# IMU_Board.net
KiCad netlist of a schematic drawn in Altium Designer
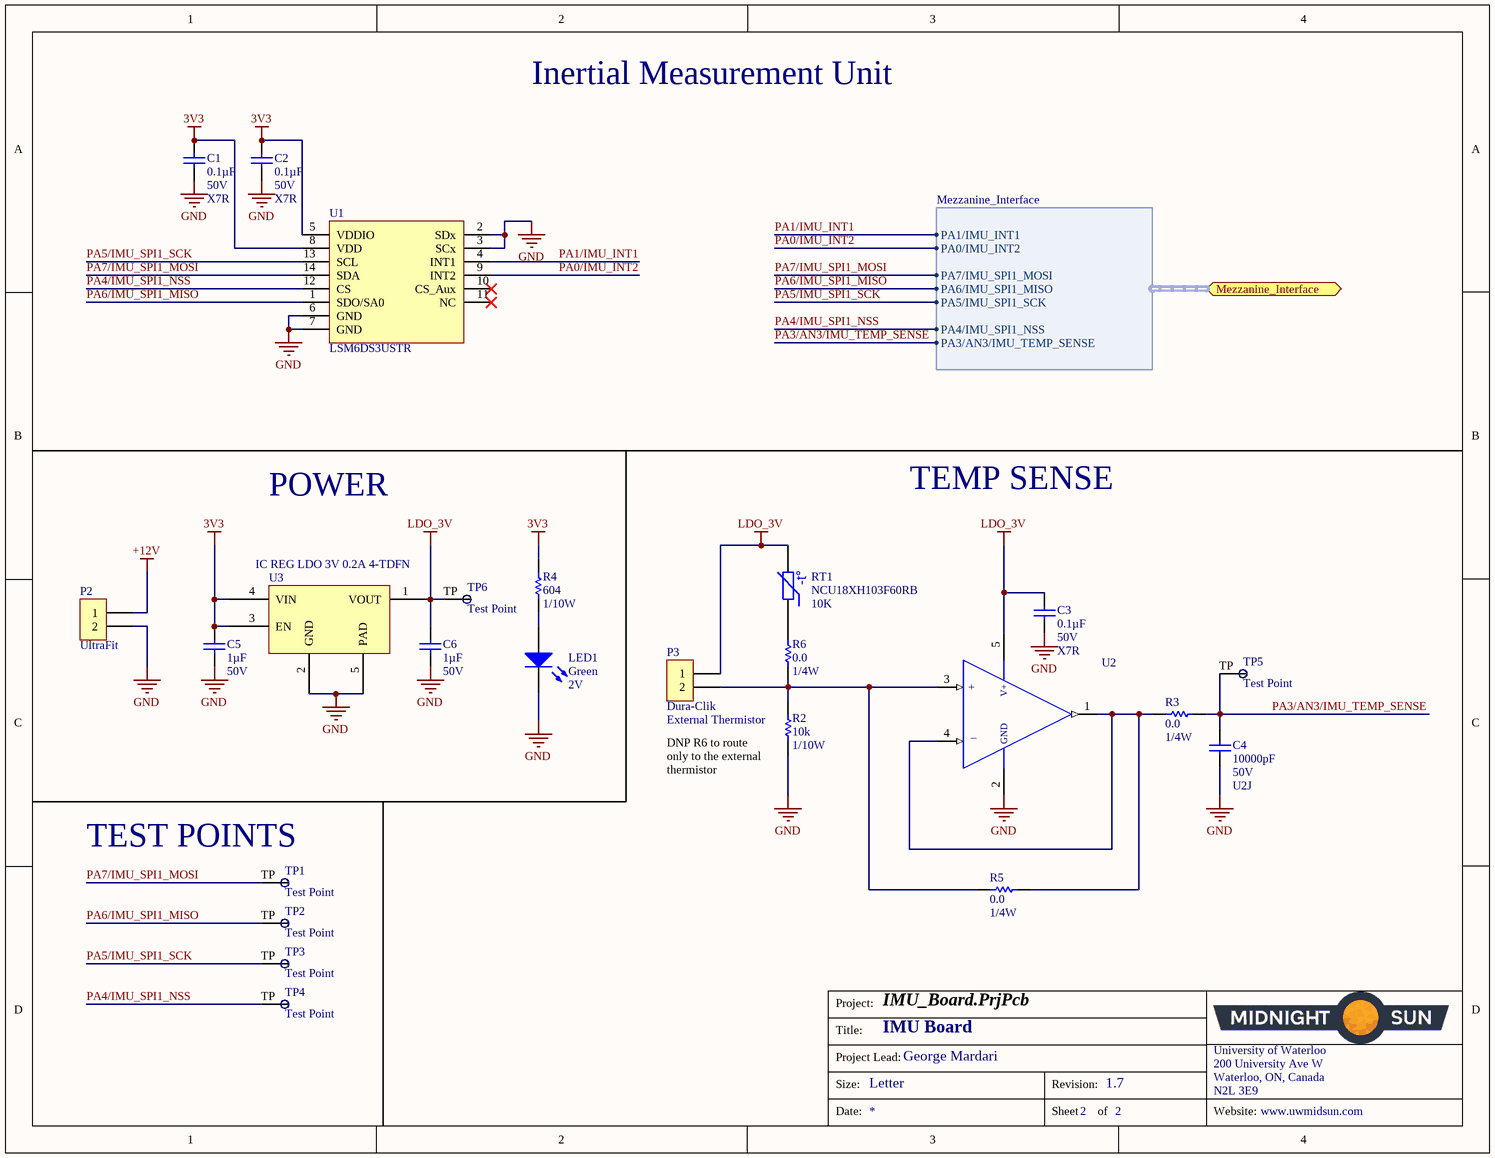
[diagram p0: IMU_Board.SchDoc]

(export (version "E")
  (design (tool "Eeschema 10.0.6"))
  (components
    (comp (ref "C1")
      (value "CAP CER 0.1UF 50V 10% X7R 0603")
      (footprint "CAP, 0603")
      (description "0.10µF ±10% 50V Ceramic Capacitor X7R 0603 (1608 Metric)")
      (fields
        (field (name "TOLERANCE") "±10%")
        (field (name "CAPACITANCE") "0.1µF")
        (field (name "VOLTAGE") "50V")
        (field (name "TEMPERATURE COEFFICIENT") "X7R")
      )
      (libsource (lib "Schematic Diagrams") (part "CAP CER 0.1UF 50V 10% X7R 0603"))
    )
    (comp (ref "C2")
      (value "CAP CER 0.1UF 50V 10% X7R 0603")
      (footprint "CAP, 0603")
      (description "0.10µF ±10% 50V Ceramic Capacitor X7R 0603 (1608 Metric)")
      (fields
        (field (name "TOLERANCE") "±10%")
        (field (name "CAPACITANCE") "0.1µF")
        (field (name "VOLTAGE") "50V")
        (field (name "TEMPERATURE COEFFICIENT") "X7R")
      )
      (libsource (lib "Schematic Diagrams") (part "CAP CER 0.1UF 50V 10% X7R 0603"))
    )
    (comp (ref "C3")
      (value "CAP CER 0.1UF 50V 10% X7R 0603")
      (footprint "CAP, 0603")
      (description "0.10µF ±10% 50V Ceramic Capacitor X7R 0603 (1608 Metric)")
      (fields
        (field (name "TOLERANCE") "±10%")
        (field (name "CAPACITANCE") "0.1µF")
        (field (name "VOLTAGE") "50V")
        (field (name "TEMPERATURE COEFFICIENT") "X7R")
      )
      (libsource (lib "Schematic Diagrams") (part "CAP CER 0.1UF 50V 10% X7R 0603"))
    )
    (comp (ref "C4")
      (value "CAP CER 10nF 50V 5% X7R 0603")
      (footprint "CAP, 0603")
      (description "10000pF ±5% 50V Ceramic Capacitor U2J 0603 (1608 Metric)")
      (fields
        (field (name "TOLERANCE") "±5%")
        (field (name "CAPACITANCE") "10000pF")
        (field (name "VOLTAGE") "50V")
        (field (name "TEMPERATURE COEFFICIENT") "U2J")
      )
      (libsource (lib "Schematic Diagrams") (part "CAP CER 10nF 50V 5% X7R 0603"))
    )
    (comp (ref "C5")
      (value "CAP CER 1UF 50V 10% X7R 0603")
      (footprint "CAP, 0603")
      (description "1µF ±10% 50V Ceramic Capacitor X7R 0603 (1608 Metric)")
      (fields
        (field (name "TOLERANCE") "±10%")
        (field (name "CAPACITANCE") "1µF")
        (field (name "VOLTAGE") "50V")
      )
      (libsource (lib "Schematic Diagrams") (part "CAP CER 1UF 50V 10% X7R 0603"))
    )
    (comp (ref "C6")
      (value "CAP CER 1UF 50V 10% X7R 0603")
      (footprint "CAP, 0603")
      (description "1µF ±10% 50V Ceramic Capacitor X7R 0603 (1608 Metric)")
      (fields
        (field (name "TOLERANCE") "±10%")
        (field (name "CAPACITANCE") "1µF")
        (field (name "VOLTAGE") "50V")
      )
      (libsource (lib "Schematic Diagrams") (part "CAP CER 1UF 50V 10% X7R 0603"))
    )
    (comp (ref "LED1")
      (value "LED GREEN CLEAR 2V 0603")
      (footprint "LED_0603")
      (description "Green 572nm LED Indication - Discrete 2V 0603 (1608 Metric)")
      (fields
        (field (name "MANUFACTURER") "Wurth Electronics Inc.")
        (field (name "MANUFACTURER PART NUMBER") "150060VS75000")
        (field (name "COLOR") "Green")
        (field (name "VOLTAGE - FORWARD (VF) (TYP)") "2V")
      )
      (libsource (lib "Schematic Diagrams") (part "LED GREEN CLEAR 2V 0603"))
    )
    (comp (ref "P2")
      (value "CONN 2POS ULTRA-FIT 0.138\"")
      (footprint "CONN, 2POS ULTRA-FIT")
      (description "2 Positions Header, Shrouded Connector 0.138\" (3.50mm) Through Hole Gold")
      (fields (field (name "VOLTAGE") "400V") (field (name "SERIES") "UltraFit"))
      (libsource (lib "Schematic Diagrams") (part "CONN 2POS ULTRA-FIT 0.138{dblquote}"))
    )
    (comp (ref "P3")
      (value "Dura-Clik")
      (footprint "CONN, 2POS Dura-Click Vertical")
      (description "2 Positions Header, Shrouded Connector 0.079\" (2.00mm) Surface Mount, Vertical Tin")
      (fields
        (field (name "MANUFACTURER") "Molex, LLC")
        (field (name "MANUFACTURER PART NUMBER") "5600200220")
      )
      (libsource (lib "Schematic Diagrams") (part "CONN 2POS DURA-CLIK 0.079{dblquote} VERT"))
    )
    (comp (ref "R2")
      (value "RES 10K OHM 1% 1/10W 0603")
      (footprint "RES, 0603")
      (description "RES SMD 10K OHM 1% 1/10W 0603")
      (fields
        (field (name "TOLERANCE") "±1%")
        (field (name "RESISTANCE") "10k")
        (field (name "POWER") "1/10W")
      )
      (libsource (lib "Schematic Diagrams") (part "RES 10K OHM 1% 1/10W 0603"))
    )
    (comp (ref "R3")
      (value "RES 0.0 OHM 1/4W 0603")
      (footprint "RES, 0603")
      (description "RES SMD 0.0 OHM JUMPER 1/4W 0603")
      (fields (field (name "RESISTANCE") "0.0") (field (name "POWER (WATTS)") "1/4W"))
      (libsource (lib "Schematic Diagrams") (part "RES 0.0 OHM 1/4W 0603"))
    )
    (comp (ref "R4")
      (value "RES 604 OHM 1% 1/10W 0603")
      (footprint "RES, 0603")
      (description "RES SMD 604 OHM 1% 1/10W 0603")
      (fields
        (field (name "TOLERANCE") "±1%")
        (field (name "RESISTANCE") "604")
        (field (name "POWER") "1/10W")
      )
      (libsource (lib "Schematic Diagrams") (part "RES 604 OHM 1% 1/10W 0603"))
    )
    (comp (ref "R5")
      (value "RES 0.0 OHM 1/4W 0603")
      (footprint "RES, 0603")
      (description "RES SMD 0.0 OHM JUMPER 1/4W 0603")
      (fields (field (name "RESISTANCE") "0.0") (field (name "POWER (WATTS)") "1/4W"))
      (libsource (lib "Schematic Diagrams") (part "RES 0.0 OHM 1/4W 0603"))
    )
    (comp (ref "R6")
      (value "RES 0.0 OHM 1/4W 0603")
      (footprint "RES, 0603")
      (description "RES SMD 0.0 OHM JUMPER 1/4W 0603")
      (fields (field (name "RESISTANCE") "0.0") (field (name "POWER (WATTS)") "1/4W"))
      (libsource (lib "Schematic Diagrams") (part "RES 0.0 OHM 1/4W 0603"))
    )
    (comp (ref "RT1")
      (value "NTC THERMISTORS 10K 0603 SMD")
      (footprint "RES, 0603")
      (description "NTC THERMISTORS 10KOHM 1608 SMD")
      (fields
        (field (name "MANUFACTURER") "Murata Electronics North America")
        (field (name "MANUFACTURER PART NUMBER") "NCU18XH103F60RB")
        (field (name "RESISTANCE") "10K")
      )
      (libsource (lib "Schematic Diagrams") (part "NTC THERMISTORS 10K 0603 SMD"))
    )
    (comp (ref "TP1")
      (value "Test Point")
      (footprint "Test Point")
      (libsource (lib "Schematic Diagrams") (part "Test Point"))
    )
    (comp (ref "TP2")
      (value "Test Point")
      (footprint "Test Point")
      (libsource (lib "Schematic Diagrams") (part "Test Point"))
    )
    (comp (ref "TP3")
      (value "Test Point")
      (footprint "Test Point")
      (libsource (lib "Schematic Diagrams") (part "Test Point"))
    )
    (comp (ref "TP4")
      (value "Test Point")
      (footprint "Test Point")
      (libsource (lib "Schematic Diagrams") (part "Test Point"))
    )
    (comp (ref "TP5")
      (value "Test Point")
      (footprint "Test Point")
      (libsource (lib "Schematic Diagrams") (part "Test Point"))
    )
    (comp (ref "TP6")
      (value "Test Point")
      (footprint "Test Point")
      (libsource (lib "Schematic Diagrams") (part "Test Point"))
    )
    (comp (ref "U1")
      (value "IC SENSOR IMU LGA-14L")
      (footprint "IC SENSOR IMU LGA-14L")
      (description "Accelerometer, Gyroscope, 3 Axis Sensor I²C, SPI Output")
      (fields
        (field (name "MANUFACTURER") "STMicroelectronics")
        (field (name "MANUFACTURER PART NUMBER") "LSM6DS3USTR")
      )
      (libsource (lib "Schematic Diagrams") (part "IC SENSOR IMU LGA-14L"))
    )
    (comp (ref "U2")
      (value "IC OP AMP GEN PURPOSE RR 10MHZ SOT-23-5")
      (footprint "IC OP AMP GP RR 10MHZ SOT-23-5")
      (description "General Purpose Amplifier 1 Circuit Rail-to-Rail SOT-23-5")
      (libsource (lib "Schematic Diagrams") (part "IC OP AMP GEN PURPOSE RR 10MHZ SOT-23-5"))
    )
    (comp (ref "U3")
      (value "IC REG LDO 3V 0.2A 4-TDFN")
      (footprint "IC REG LDO 3V 0.2A 4-TDFN")
      (fields
        (field (name "MANUFACTURER") "Microchip Technology")
        (field (name "MANUFACTURER PART NUMBER") "MIC94310-PYMT-TR")
      )
      (libsource (lib "Schematic Diagrams") (part "IC REG LDO 3V 0.2A 4-TDFN"))
    )
  )
  (nets
    (net (code "2") (name "+12V") (class "Default")
      (node (ref "P2") (pin "1") (pinfunction "1_1") (pintype "passive"))
    )
    (net (code "3") (name "/PA0{slash}IMU_INT2") (class "Default")
      (node (ref "U1") (pin "9") (pinfunction "INT2_9") (pintype "passive"))
    )
    (net (code "4") (name "/PA1{slash}IMU_INT1") (class "Default")
      (node (ref "U1") (pin "4") (pinfunction "INT1_4") (pintype "passive"))
    )
    (net (code "5") (name "/PA3{slash}AN3{slash}IMU_TEMP_SENSE") (class "Default")
      (node (ref "C4") (pin "1") (pinfunction "1_1") (pintype "passive"))
      (node (ref "R3") (pin "2") (pinfunction "2_2") (pintype "passive"))
      (node (ref "TP5") (pin "TP") (pinfunction "1_TP") (pintype "passive"))
    )
    (net (code "6") (name "/PA4{slash}IMU_SPI1_NSS") (class "Default")
      (node (ref "TP4") (pin "TP") (pinfunction "1_TP") (pintype "passive"))
      (node (ref "U1") (pin "12") (pinfunction "CS_12") (pintype "passive"))
    )
    (net (code "7") (name "/PA5{slash}IMU_SPI1_SCK") (class "Default")
      (node (ref "TP3") (pin "TP") (pinfunction "1_TP") (pintype "passive"))
      (node (ref "U1") (pin "13") (pinfunction "SCL_13") (pintype "passive"))
    )
    (net (code "8") (name "/PA6{slash}IMU_SPI1_MISO") (class "Default")
      (node (ref "TP2") (pin "TP") (pinfunction "1_TP") (pintype "passive"))
      (node (ref "U1") (pin "1") (pinfunction "SDO/SA0_1") (pintype "passive"))
    )
    (net (code "9") (name "/PA7{slash}IMU_SPI1_MOSI") (class "Default")
      (node (ref "TP1") (pin "TP") (pinfunction "1_TP") (pintype "passive"))
      (node (ref "U1") (pin "14") (pinfunction "SDA_14") (pintype "passive"))
    )
    (net (code "11") (name "3V3") (class "Default")
      (node (ref "C1") (pin "1") (pinfunction "1_1") (pintype "passive"))
      (node (ref "C2") (pin "1") (pinfunction "1_1") (pintype "passive"))
      (node (ref "C5") (pin "1") (pinfunction "1_1") (pintype "passive"))
      (node (ref "R4") (pin "1") (pinfunction "1_1") (pintype "passive"))
      (node (ref "U1") (pin "5") (pinfunction "VDDIO_5") (pintype "passive"))
      (node (ref "U1") (pin "8") (pinfunction "VDD_8") (pintype "passive"))
      (node (ref "U3") (pin "3") (pinfunction "EN_3") (pintype "passive"))
      (node (ref "U3") (pin "4") (pinfunction "VIN_4") (pintype "passive"))
    )
    (net (code "12") (name "GND") (class "Default")
      (node (ref "C1") (pin "2") (pinfunction "2_2") (pintype "passive"))
      (node (ref "C2") (pin "2") (pinfunction "2_2") (pintype "passive"))
      (node (ref "C3") (pin "2") (pinfunction "2_2") (pintype "passive"))
      (node (ref "C4") (pin "2") (pinfunction "2_2") (pintype "passive"))
      (node (ref "C5") (pin "2") (pinfunction "2_2") (pintype "passive"))
      (node (ref "C6") (pin "2") (pinfunction "2_2") (pintype "passive"))
      (node (ref "LED1") (pin "2") (pinfunction "K_2") (pintype "passive"))
      (node (ref "P2") (pin "2") (pinfunction "2_2") (pintype "passive"))
      (node (ref "R2") (pin "1") (pinfunction "1_1") (pintype "passive"))
      (node (ref "U1") (pin "2") (pinfunction "SDx_2") (pintype "passive"))
      (node (ref "U1") (pin "3") (pinfunction "SCx_3") (pintype "passive"))
      (node (ref "U1") (pin "6") (pinfunction "GND_6") (pintype "passive"))
      (node (ref "U1") (pin "7") (pinfunction "GND_7") (pintype "passive"))
      (node (ref "U2") (pin "2") (pinfunction "VSS_2") (pintype "power_in"))
      (node (ref "U3") (pin "2") (pinfunction "GND_2") (pintype "passive"))
      (node (ref "U3") (pin "5") (pinfunction "PAD_5") (pintype "passive"))
    )
    (net (code "13") (name "LDO_3V") (class "Default")
      (node (ref "C3") (pin "1") (pinfunction "1_1") (pintype "passive"))
      (node (ref "C6") (pin "1") (pinfunction "1_1") (pintype "passive"))
      (node (ref "P3") (pin "1") (pinfunction "1_1") (pintype "passive"))
      (node (ref "RT1") (pin "2") (pinfunction "2_2") (pintype "passive"))
      (node (ref "TP6") (pin "TP") (pinfunction "1_TP") (pintype "passive"))
      (node (ref "U2") (pin "5") (pinfunction "VDD_5") (pintype "power_in"))
      (node (ref "U3") (pin "1") (pinfunction "VOUT_1") (pintype "passive"))
    )
    (net (code "14") (name "Net-(LED1-A)") (class "Default")
      (node (ref "LED1") (pin "1") (pinfunction "A_1") (pintype "passive"))
      (node (ref "R4") (pin "2") (pinfunction "2_2") (pintype "passive"))
    )
    (net (code "15") (name "Net-(R6-Pad1)") (class "Default")
      (node (ref "R6") (pin "1") (pinfunction "1_1") (pintype "passive"))
      (node (ref "RT1") (pin "1") (pinfunction "1_1") (pintype "passive"))
    )
    (net (code "16") (name "Net-(U2-+IN)") (class "Default")
      (node (ref "P3") (pin "2") (pinfunction "2_2") (pintype "passive"))
      (node (ref "R2") (pin "2") (pinfunction "2_2") (pintype "passive"))
      (node (ref "R5") (pin "1") (pinfunction "1_1") (pintype "passive"))
      (node (ref "R6") (pin "2") (pinfunction "2_2") (pintype "passive"))
      (node (ref "U2") (pin "3") (pinfunction "+IN_3") (pintype "input"))
    )
    (net (code "17") (name "Net-(U2--IN)") (class "Default")
      (node (ref "R3") (pin "1") (pinfunction "1_1") (pintype "passive"))
      (node (ref "R5") (pin "2") (pinfunction "2_2") (pintype "passive"))
      (node (ref "U2") (pin "1") (pinfunction "OUTPUT_1") (pintype "output"))
      (node (ref "U2") (pin "4") (pinfunction "-IN_4") (pintype "input"))
    )
    (net (code "18") (name "unconnected-(U1-CS_Aux-Pad10)") (class "Default")
      (node (ref "U1") (pin "10") (pinfunction "CS_Aux_10") (pintype "passive+no_connect"))
    )
    (net (code "19") (name "unconnected-(U1-NC-Pad11)") (class "Default")
      (node (ref "U1") (pin "11") (pinfunction "NC_11") (pintype "passive+no_connect"))
    )
  )
)
